# Remotuino-v3.net
KiCad netlist of a schematic drawn in EAGLE
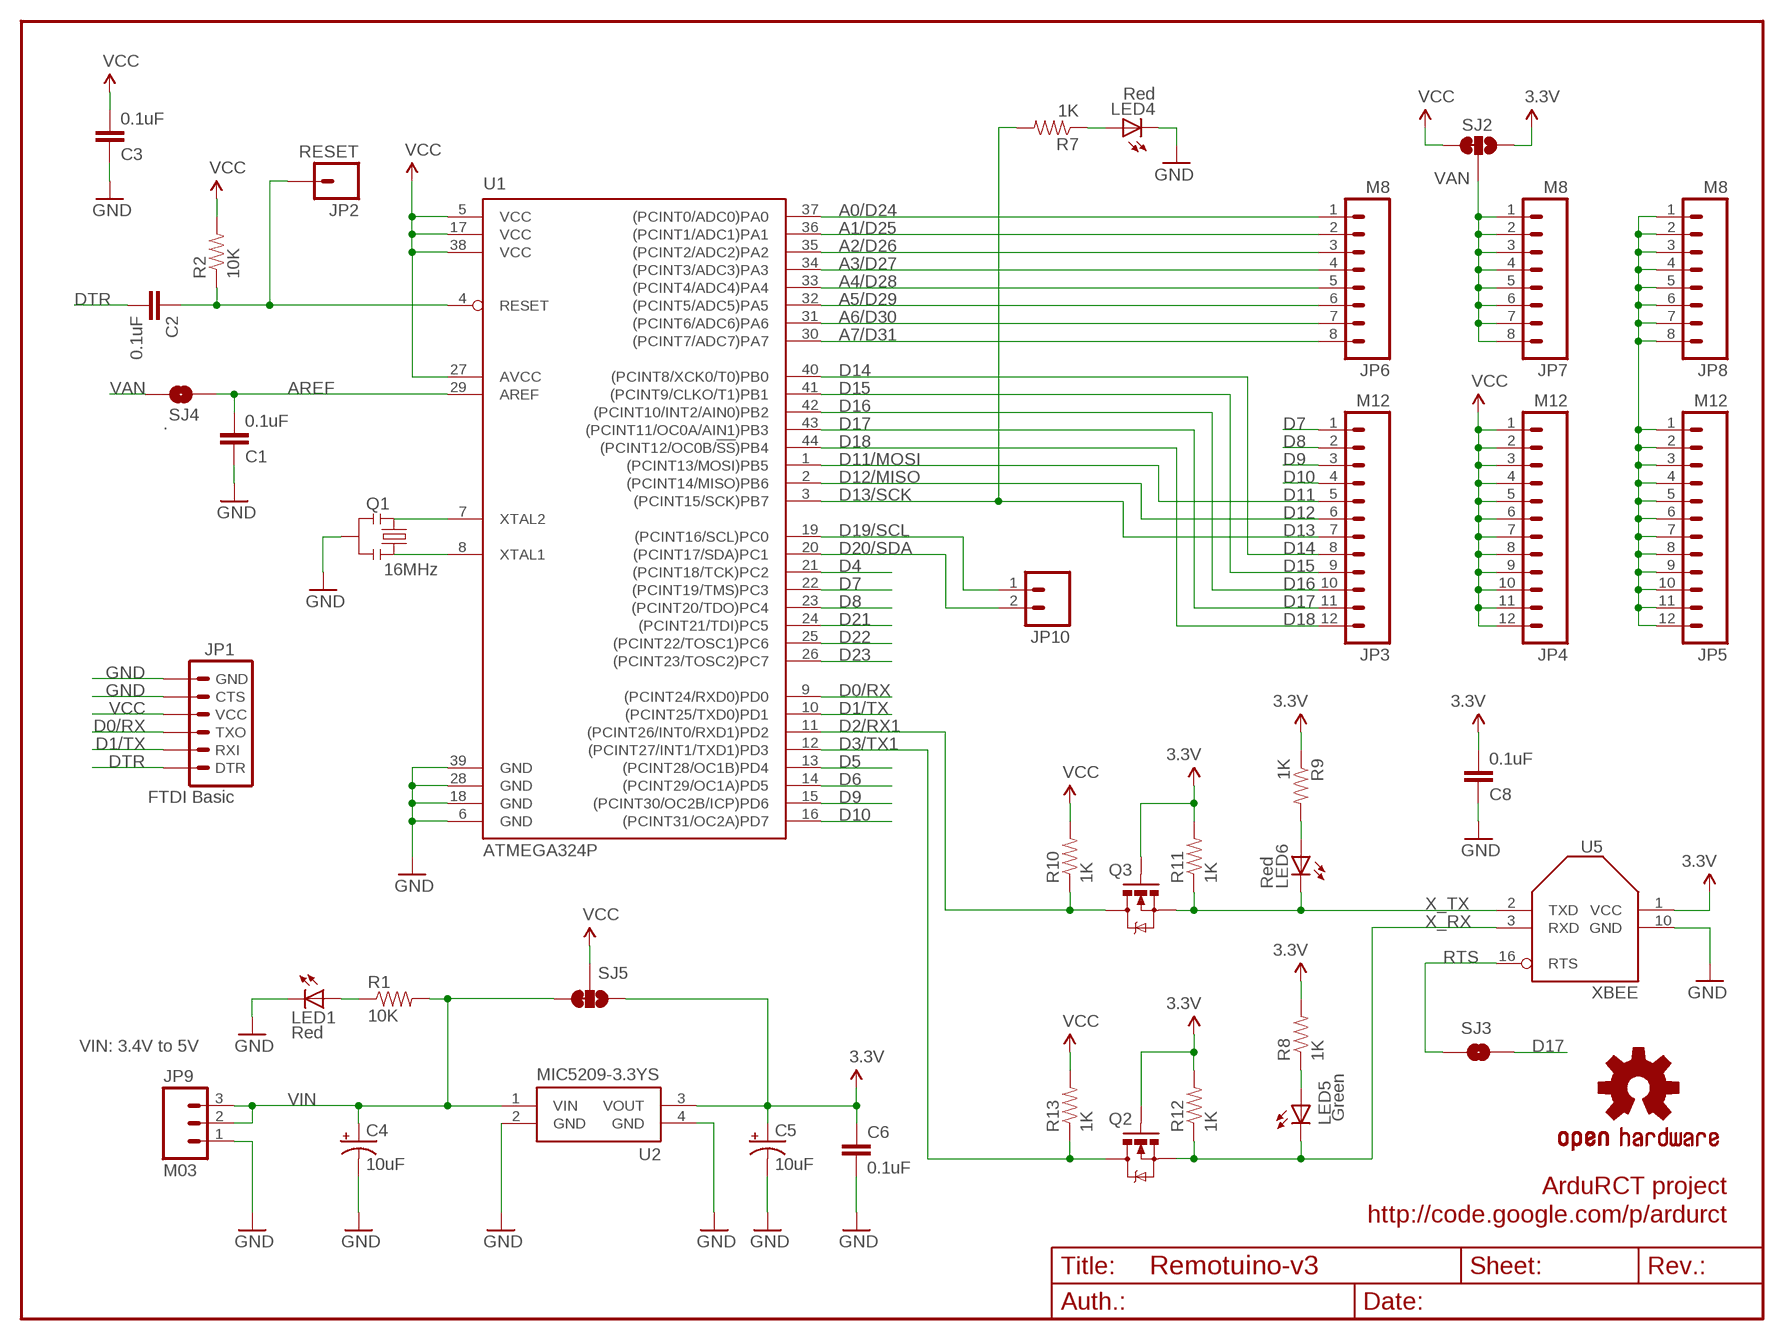
[diagram p0: schematic, sheet 1]

(export (version "E")
  (design (tool "Eeschema 10.0.6"))
  (components
    (comp (ref "C1")
      (value "0.1uF")
      (footprint "eagle-import:0805")
      (libsource (lib "eagle-import") (part "CAP0805"))
    )
    (comp (ref "C2")
      (value "0.1uF")
      (footprint "eagle-import:0805")
      (libsource (lib "eagle-import") (part "CAP0805"))
    )
    (comp (ref "C3")
      (value "0.1uF")
      (footprint "eagle-import:0805")
      (libsource (lib "eagle-import") (part "CAP0805"))
    )
    (comp (ref "C4")
      (value "10uF")
      (footprint "eagle-import:EIA3216")
      (libsource (lib "eagle-import") (part "CAP_POL1206"))
    )
    (comp (ref "C5")
      (value "10uF")
      (footprint "eagle-import:EIA3216")
      (libsource (lib "eagle-import") (part "CAP_POL1206"))
    )
    (comp (ref "C6")
      (value "0.1uF")
      (footprint "eagle-import:0805")
      (libsource (lib "eagle-import") (part "CAP0805"))
    )
    (comp (ref "C8")
      (value "0.1uF")
      (footprint "eagle-import:0805")
      (libsource (lib "eagle-import") (part "CAP0805"))
    )
    (comp (ref "JP1")
      (value "FTDI Basic")
      (footprint "eagle-import:1X06")
      (libsource (lib "eagle-import") (part "ARDUINO_SERIAL_PROGRAMPTH"))
    )
    (comp (ref "JP2")
      (value "RESET")
      (footprint "eagle-import:1X01")
      (libsource (lib "eagle-import") (part "M01PTH"))
    )
    (comp (ref "JP3")
      (value "M12")
      (footprint "eagle-import:1X12")
      (libsource (lib "eagle-import") (part "M12PTH"))
    )
    (comp (ref "JP4")
      (value "M12")
      (footprint "eagle-import:1X12")
      (libsource (lib "eagle-import") (part "M12PTH"))
    )
    (comp (ref "JP5")
      (value "M12")
      (footprint "eagle-import:1X12")
      (libsource (lib "eagle-import") (part "M12PTH"))
    )
    (comp (ref "JP6")
      (value "M8")
      (footprint "eagle-import:1X08")
      (libsource (lib "eagle-import") (part "M08"))
    )
    (comp (ref "JP7")
      (value "M8")
      (footprint "eagle-import:1X08")
      (libsource (lib "eagle-import") (part "M08"))
    )
    (comp (ref "JP8")
      (value "M8")
      (footprint "eagle-import:1X08")
      (libsource (lib "eagle-import") (part "M08"))
    )
    (comp (ref "JP9")
      (value "M03")
      (footprint "eagle-import:1X3_LONGPAD")
      (libsource (lib "eagle-import") (part "M03"))
    )
    (comp (ref "JP10")
      (value "M02")
      (footprint "eagle-import:1X02")
      (libsource (lib "eagle-import") (part "M02"))
    )
    (comp (ref "LED1")
      (value "Red")
      (footprint "eagle-import:LED-0805")
      (libsource (lib "eagle-import") (part "LED805"))
    )
    (comp (ref "LED4")
      (value "Red")
      (footprint "eagle-import:LED-0805")
      (libsource (lib "eagle-import") (part "LED805"))
    )
    (comp (ref "LED5")
      (value "Green")
      (footprint "eagle-import:LED-0805")
      (libsource (lib "eagle-import") (part "LED805"))
    )
    (comp (ref "LED6")
      (value "Red")
      (footprint "eagle-import:LED-0805")
      (libsource (lib "eagle-import") (part "LED805"))
    )
    (comp (ref "Q1")
      (value "16MHz")
      (footprint "eagle-import:RESONATOR-SMD")
      (libsource (lib "eagle-import") (part "RESONATORSMD"))
    )
    (comp (ref "Q2")
      (value "BSS138")
      (footprint "eagle-import:SOT23-3")
      (libsource (lib "eagle-import") (part "MOSFET-NCHANNELSMD"))
    )
    (comp (ref "Q3")
      (value "BSS138")
      (footprint "eagle-import:SOT23-3")
      (libsource (lib "eagle-import") (part "MOSFET-NCHANNELSMD"))
    )
    (comp (ref "R1")
      (value "10K")
      (footprint "eagle-import:0805")
      (libsource (lib "eagle-import") (part "RESISTOR0805-RES"))
    )
    (comp (ref "R2")
      (value "10K")
      (footprint "eagle-import:0805")
      (libsource (lib "eagle-import") (part "RESISTOR0805-RES"))
    )
    (comp (ref "R7")
      (value "1K")
      (footprint "eagle-import:0805")
      (libsource (lib "eagle-import") (part "RESISTOR0805-RES"))
    )
    (comp (ref "R8")
      (value "1K")
      (footprint "eagle-import:0805")
      (libsource (lib "eagle-import") (part "RESISTOR0805-RES"))
    )
    (comp (ref "R9")
      (value "1K")
      (footprint "eagle-import:0805")
      (libsource (lib "eagle-import") (part "RESISTOR0805-RES"))
    )
    (comp (ref "R10")
      (value "1K")
      (footprint "eagle-import:0805")
      (libsource (lib "eagle-import") (part "RESISTOR0805-RES"))
    )
    (comp (ref "R11")
      (value "1K")
      (footprint "eagle-import:0805")
      (libsource (lib "eagle-import") (part "RESISTOR0805-RES"))
    )
    (comp (ref "R12")
      (value "1K")
      (footprint "eagle-import:0805")
      (libsource (lib "eagle-import") (part "RESISTOR0805-RES"))
    )
    (comp (ref "R13")
      (value "1K")
      (footprint "eagle-import:0805")
      (libsource (lib "eagle-import") (part "RESISTOR0805-RES"))
    )
    (comp (ref "SJ2")
      (value "SJ_2WAYS_1-2W")
      (footprint "eagle-import:SJ_2WAYS_1-2")
      (libsource (lib "eagle-import") (part "SJ_2WAYS_1-2W"))
    )
    (comp (ref "SJ3")
      (value "SOLDERJUMPERNO")
      (footprint "eagle-import:SJ_2S-NO")
      (libsource (lib "eagle-import") (part "SOLDERJUMPERNO"))
    )
    (comp (ref "SJ4")
      (value ".")
      (footprint "eagle-import:SJ_2S-TRACE")
      (libsource (lib "eagle-import") (part "SOLDERJUMPERTRACE"))
    )
    (comp (ref "SJ5")
      (value "SJ_2WAYS_1-2W")
      (footprint "eagle-import:SJ_2WAYS_1-2")
      (libsource (lib "eagle-import") (part "SJ_2WAYS_1-2W"))
    )
    (comp (ref "U$3")
      (value "OSHW-LOGOS")
      (footprint "eagle-import:OSHW-LOGO-S")
      (libsource (lib "eagle-import") (part "OSHW-LOGOS"))
    )
    (comp (ref "U1")
      (value "ATMEGA324P")
      (footprint "eagle-import:TQFP44")
      (libsource (lib "eagle-import") (part "ATMEGA324A"))
    )
    (comp (ref "U2")
      (value "MIC5209-3.3YS")
      (footprint "eagle-import:SOT223")
      (libsource (lib "eagle-import") (part "MIC5209"))
    )
    (comp (ref "U5")
      (value "XBEE")
      (footprint "eagle-import:XBEE-SMD")
      (libsource (lib "eagle-import") (part "XBEE-SIMPLESMD"))
    )
  )
  (nets
    (net (code "1") (name "/A0{slash}D24") (class "Default")
      (node (ref "JP6") (pin "1") (pinfunction "1_1") (pintype "passive"))
      (node (ref "U1") (pin "37") (pinfunction "(PCINT0/ADC0)PA0_37") (pintype "bidirectional"))
    )
    (net (code "2") (name "/A1{slash}D25") (class "Default")
      (node (ref "JP6") (pin "2") (pinfunction "2_2") (pintype "passive"))
      (node (ref "U1") (pin "36") (pinfunction "(PCINT1/ADC1)PA1_36") (pintype "bidirectional"))
    )
    (net (code "3") (name "/A2{slash}D26") (class "Default")
      (node (ref "JP6") (pin "3") (pinfunction "3_3") (pintype "passive"))
      (node (ref "U1") (pin "35") (pinfunction "(PCINT2/ADC2)PA2_35") (pintype "bidirectional"))
    )
    (net (code "4") (name "/A3{slash}D27") (class "Default")
      (node (ref "JP6") (pin "4") (pinfunction "4_4") (pintype "passive"))
      (node (ref "U1") (pin "34") (pinfunction "(PCINT3/ADC3)PA3_34") (pintype "bidirectional"))
    )
    (net (code "5") (name "/A4{slash}D28") (class "Default")
      (node (ref "JP6") (pin "5") (pinfunction "5_5") (pintype "passive"))
      (node (ref "U1") (pin "33") (pinfunction "(PCINT4/ADC4)PA4_33") (pintype "bidirectional"))
    )
    (net (code "6") (name "/A5{slash}D29") (class "Default")
      (node (ref "JP6") (pin "6") (pinfunction "6_6") (pintype "passive"))
      (node (ref "U1") (pin "32") (pinfunction "(PCINT5/ADC5)PA5_32") (pintype "bidirectional"))
    )
    (net (code "7") (name "/A6{slash}D30") (class "Default")
      (node (ref "JP6") (pin "7") (pinfunction "7_7") (pintype "passive"))
      (node (ref "U1") (pin "31") (pinfunction "(PCINT6/ADC6)PA6_31") (pintype "bidirectional"))
    )
    (net (code "8") (name "/A7{slash}D31") (class "Default")
      (node (ref "JP6") (pin "8") (pinfunction "8_8") (pintype "passive"))
      (node (ref "U1") (pin "30") (pinfunction "(PCINT7/ADC7)PA7_30") (pintype "bidirectional"))
    )
    (net (code "9") (name "/AREF") (class "Default")
      (node (ref "C1") (pin "2") (pinfunction "2_2") (pintype "passive"))
      (node (ref "SJ4") (pin "2") (pinfunction "2_2") (pintype "passive"))
      (node (ref "U1") (pin "29") (pinfunction "AREF_29") (pintype "passive"))
    )
    (net (code "10") (name "/D0{slash}RX") (class "Default")
      (node (ref "JP1") (pin "3") (pinfunction "TXO_3") (pintype "passive"))
      (node (ref "U1") (pin "9") (pinfunction "(PCINT24/RXD0)PD0_9") (pintype "bidirectional"))
    )
    (net (code "11") (name "/D1{slash}TX") (class "Default")
      (node (ref "JP1") (pin "2") (pinfunction "RXI_2") (pintype "passive"))
      (node (ref "U1") (pin "10") (pinfunction "(PCINT25/TXD0)PD1_10") (pintype "bidirectional"))
    )
    (net (code "12") (name "/D2{slash}RX1") (class "Default")
      (node (ref "Q3") (pin "3") (pinfunction "D_3") (pintype "passive"))
      (node (ref "R10") (pin "1") (pinfunction "1_1") (pintype "passive"))
      (node (ref "U1") (pin "11") (pinfunction "(PCINT26/INT0/RXD1)PD2_11") (pintype "bidirectional"))
    )
    (net (code "13") (name "/D3{slash}TX1") (class "Default")
      (node (ref "Q2") (pin "3") (pinfunction "D_3") (pintype "passive"))
      (node (ref "R13") (pin "1") (pinfunction "1_1") (pintype "passive"))
      (node (ref "U1") (pin "12") (pinfunction "(PCINT27/INT1/TXD1)PD3_12") (pintype "bidirectional"))
    )
    (net (code "14") (name "/D4") (class "Default")
      (node (ref "U1") (pin "21") (pinfunction "(PCINT18/TCK)PC2_21") (pintype "output"))
    )
    (net (code "15") (name "/D5") (class "Default")
      (node (ref "U1") (pin "13") (pinfunction "(PCINT28/OC1B)PD4_13") (pintype "bidirectional"))
    )
    (net (code "16") (name "/D6") (class "Default")
      (node (ref "U1") (pin "14") (pinfunction "(PCINT29/OC1A)PD5_14") (pintype "bidirectional"))
    )
    (net (code "17") (name "/D7") (class "Default")
      (node (ref "JP3") (pin "1") (pinfunction "1_1") (pintype "passive"))
      (node (ref "U1") (pin "22") (pinfunction "(PCINT19/TMS)PC3_22") (pintype "output"))
    )
    (net (code "18") (name "/D8") (class "Default")
      (node (ref "JP3") (pin "2") (pinfunction "2_2") (pintype "passive"))
      (node (ref "U1") (pin "23") (pinfunction "(PCINT20/TDO)PC4_23") (pintype "output"))
    )
    (net (code "19") (name "/D9") (class "Default")
      (node (ref "JP3") (pin "3") (pinfunction "3_3") (pintype "passive"))
      (node (ref "U1") (pin "15") (pinfunction "(PCINT30/OC2B/ICP)PD6_15") (pintype "bidirectional"))
    )
    (net (code "20") (name "/D10") (class "Default")
      (node (ref "JP3") (pin "4") (pinfunction "4_4") (pintype "passive"))
      (node (ref "U1") (pin "16") (pinfunction "(PCINT31/OC2A)PD7_16") (pintype "bidirectional"))
    )
    (net (code "21") (name "/D11{slash}MOSI") (class "Default")
      (node (ref "JP3") (pin "5") (pinfunction "5_5") (pintype "passive"))
      (node (ref "U1") (pin "1") (pinfunction "(PCINT13/MOSI)PB5_1") (pintype "bidirectional"))
    )
    (net (code "22") (name "/D12{slash}MISO") (class "Default")
      (node (ref "JP3") (pin "6") (pinfunction "6_6") (pintype "passive"))
      (node (ref "U1") (pin "2") (pinfunction "(PCINT14/MISO)PB6_2") (pintype "bidirectional"))
    )
    (net (code "23") (name "/D13{slash}SCK") (class "Default")
      (node (ref "JP3") (pin "7") (pinfunction "7_7") (pintype "passive"))
      (node (ref "R7") (pin "2") (pinfunction "2_2") (pintype "passive"))
      (node (ref "U1") (pin "3") (pinfunction "(PCINT15/SCK)PB7_3") (pintype "bidirectional"))
    )
    (net (code "24") (name "/D14") (class "Default")
      (node (ref "JP3") (pin "8") (pinfunction "8_8") (pintype "passive"))
      (node (ref "U1") (pin "40") (pinfunction "(PCINT8/XCK0/T0)PB0_40") (pintype "bidirectional"))
    )
    (net (code "25") (name "/D15") (class "Default")
      (node (ref "JP3") (pin "9") (pinfunction "9_9") (pintype "passive"))
      (node (ref "U1") (pin "41") (pinfunction "(PCINT9/CLKO/T1)PB1_41") (pintype "bidirectional"))
    )
    (net (code "26") (name "/D16") (class "Default")
      (node (ref "JP3") (pin "10") (pinfunction "10_10") (pintype "passive"))
      (node (ref "U1") (pin "42") (pinfunction "(PCINT10/INT2/AIN0)PB2_42") (pintype "bidirectional"))
    )
    (net (code "27") (name "/D17") (class "Default")
      (node (ref "JP3") (pin "11") (pinfunction "11_11") (pintype "passive"))
      (node (ref "SJ3") (pin "2") (pinfunction "2_2") (pintype "passive"))
      (node (ref "U1") (pin "43") (pinfunction "(PCINT11/OC0A/AIN1)PB3_43") (pintype "bidirectional"))
    )
    (net (code "28") (name "/D18") (class "Default")
      (node (ref "JP3") (pin "12") (pinfunction "12_12") (pintype "passive"))
      (node (ref "U1") (pin "44") (pinfunction "(PCINT12/OC0B/~{SS})PB4_44") (pintype "bidirectional"))
    )
    (net (code "29") (name "/D19{slash}SCL") (class "Default")
      (node (ref "JP10") (pin "1") (pinfunction "1_1") (pintype "passive"))
      (node (ref "U1") (pin "19") (pinfunction "(PCINT16/SCL)PC0_19") (pintype "output"))
    )
    (net (code "30") (name "/D20{slash}SDA") (class "Default")
      (node (ref "JP10") (pin "2") (pinfunction "2_2") (pintype "passive"))
      (node (ref "U1") (pin "20") (pinfunction "(PCINT17/SDA)PC1_20") (pintype "output"))
    )
    (net (code "31") (name "/D21") (class "Default")
      (node (ref "U1") (pin "24") (pinfunction "(PCINT21/TDI)PC5_24") (pintype "output"))
    )
    (net (code "32") (name "/D22") (class "Default")
      (node (ref "U1") (pin "25") (pinfunction "(PCINT22/TOSC1)PC6_25") (pintype "output"))
    )
    (net (code "33") (name "/D23") (class "Default")
      (node (ref "U1") (pin "26") (pinfunction "(PCINT23/TOSC2)PC7_26") (pintype "output"))
    )
    (net (code "34") (name "/DTR") (class "Default")
      (node (ref "C2") (pin "2") (pinfunction "2_2") (pintype "passive"))
      (node (ref "JP1") (pin "1") (pinfunction "DTR_1") (pintype "passive"))
    )
    (net (code "35") (name "/RTS") (class "Default")
      (node (ref "SJ3") (pin "1") (pinfunction "1_1") (pintype "passive"))
      (node (ref "U5") (pin "16") (pinfunction "RTS_16") (pintype "bidirectional"))
    )
    (net (code "36") (name "/VAN") (class "Default")
      (node (ref "JP7") (pin "1") (pinfunction "1_1") (pintype "passive"))
      (node (ref "JP7") (pin "2") (pinfunction "2_2") (pintype "passive"))
      (node (ref "JP7") (pin "3") (pinfunction "3_3") (pintype "passive"))
      (node (ref "JP7") (pin "4") (pinfunction "4_4") (pintype "passive"))
      (node (ref "JP7") (pin "5") (pinfunction "5_5") (pintype "passive"))
      (node (ref "JP7") (pin "6") (pinfunction "6_6") (pintype "passive"))
      (node (ref "JP7") (pin "7") (pinfunction "7_7") (pintype "passive"))
      (node (ref "JP7") (pin "8") (pinfunction "8_8") (pintype "passive"))
      (node (ref "SJ2") (pin "2") (pinfunction "2_2") (pintype "passive"))
      (node (ref "SJ4") (pin "1") (pinfunction "1_1") (pintype "passive"))
    )
    (net (code "37") (name "/VIN") (class "Default")
      (node (ref "C4") (pin "A") (pinfunction "+_A") (pintype "passive"))
      (node (ref "JP9") (pin "2") (pinfunction "2_2") (pintype "passive"))
      (node (ref "JP9") (pin "3") (pinfunction "3_3") (pintype "passive"))
      (node (ref "R1") (pin "2") (pinfunction "2_2") (pintype "passive"))
      (node (ref "SJ5") (pin "1") (pinfunction "1_1") (pintype "passive"))
      (node (ref "U2") (pin "1") (pinfunction "VIN_1") (pintype "bidirectional"))
    )
    (net (code "38") (name "/X_RX") (class "Default")
      (node (ref "LED5") (pin "2") (pinfunction "C_2") (pintype "passive"))
      (node (ref "Q2") (pin "2") (pinfunction "S_2") (pintype "passive"))
      (node (ref "R12") (pin "1") (pinfunction "1_1") (pintype "passive"))
      (node (ref "U5") (pin "3") (pinfunction "RXD_3") (pintype "bidirectional"))
    )
    (net (code "39") (name "/X_TX") (class "Default")
      (node (ref "LED6") (pin "2") (pinfunction "C_2") (pintype "passive"))
      (node (ref "Q3") (pin "2") (pinfunction "S_2") (pintype "passive"))
      (node (ref "R11") (pin "1") (pinfunction "1_1") (pintype "passive"))
      (node (ref "U5") (pin "2") (pinfunction "TXD_2") (pintype "bidirectional"))
    )
    (net (code "40") (name "3.3V") (class "Default")
      (node (ref "C5") (pin "A") (pinfunction "+_A") (pintype "passive"))
      (node (ref "C6") (pin "1") (pinfunction "1_1") (pintype "passive"))
      (node (ref "C8") (pin "2") (pinfunction "2_2") (pintype "passive"))
      (node (ref "Q2") (pin "1") (pinfunction "G_1") (pintype "passive"))
      (node (ref "Q3") (pin "1") (pinfunction "G_1") (pintype "passive"))
      (node (ref "R11") (pin "2") (pinfunction "2_2") (pintype "passive"))
      (node (ref "R12") (pin "2") (pinfunction "2_2") (pintype "passive"))
      (node (ref "R8") (pin "2") (pinfunction "2_2") (pintype "passive"))
      (node (ref "R9") (pin "1") (pinfunction "1_1") (pintype "passive"))
      (node (ref "SJ2") (pin "3") (pinfunction "3_3") (pintype "passive"))
      (node (ref "SJ5") (pin "3") (pinfunction "3_3") (pintype "passive"))
      (node (ref "U2") (pin "3") (pinfunction "VOUT_3") (pintype "bidirectional"))
      (node (ref "U5") (pin "1") (pinfunction "VCC_1") (pintype "bidirectional"))
    )
    (net (code "41") (name "GND") (class "Default")
      (node (ref "C1") (pin "1") (pinfunction "1_1") (pintype "passive"))
      (node (ref "C3") (pin "1") (pinfunction "1_1") (pintype "passive"))
      (node (ref "C4") (pin "C") (pinfunction "-_C") (pintype "passive"))
      (node (ref "C5") (pin "C") (pinfunction "-_C") (pintype "passive"))
      (node (ref "C6") (pin "2") (pinfunction "2_2") (pintype "passive"))
      (node (ref "C8") (pin "1") (pinfunction "1_1") (pintype "passive"))
      (node (ref "JP1") (pin "5") (pinfunction "CTS_5") (pintype "passive"))
      (node (ref "JP1") (pin "6") (pinfunction "GND_6") (pintype "passive"))
      (node (ref "JP9") (pin "1") (pinfunction "1_1") (pintype "passive"))
      (node (ref "LED1") (pin "2") (pinfunction "C_2") (pintype "passive"))
      (node (ref "LED4") (pin "2") (pinfunction "C_2") (pintype "passive"))
      (node (ref "Q1") (pin "2") (pinfunction "2_2") (pintype "passive"))
      (node (ref "U1") (pin "18") (pinfunction "GND_18") (pintype "power_in"))
      (node (ref "U1") (pin "28") (pinfunction "GND_28") (pintype "power_in"))
      (node (ref "U1") (pin "39") (pinfunction "GND_39") (pintype "power_in"))
      (node (ref "U1") (pin "6") (pinfunction "GND_6") (pintype "power_in"))
      (node (ref "U2") (pin "2") (pinfunction "GND_2") (pintype "bidirectional"))
      (node (ref "U2") (pin "4") (pinfunction "GND_4") (pintype "bidirectional"))
      (node (ref "U5") (pin "10") (pinfunction "GND_10") (pintype "bidirectional"))
    )
    (net (code "42") (name "Net-(JP5-Pad1)") (class "Default")
      (node (ref "JP5") (pin "1") (pinfunction "1_1") (pintype "passive"))
      (node (ref "JP5") (pin "10") (pinfunction "10_10") (pintype "passive"))
      (node (ref "JP5") (pin "11") (pinfunction "11_11") (pintype "passive"))
      (node (ref "JP5") (pin "12") (pinfunction "12_12") (pintype "passive"))
      (node (ref "JP5") (pin "2") (pinfunction "2_2") (pintype "passive"))
      (node (ref "JP5") (pin "3") (pinfunction "3_3") (pintype "passive"))
      (node (ref "JP5") (pin "4") (pinfunction "4_4") (pintype "passive"))
      (node (ref "JP5") (pin "5") (pinfunction "5_5") (pintype "passive"))
      (node (ref "JP5") (pin "6") (pinfunction "6_6") (pintype "passive"))
      (node (ref "JP5") (pin "7") (pinfunction "7_7") (pintype "passive"))
      (node (ref "JP5") (pin "8") (pinfunction "8_8") (pintype "passive"))
      (node (ref "JP5") (pin "9") (pinfunction "9_9") (pintype "passive"))
      (node (ref "JP8") (pin "1") (pinfunction "1_1") (pintype "passive"))
      (node (ref "JP8") (pin "2") (pinfunction "2_2") (pintype "passive"))
      (node (ref "JP8") (pin "3") (pinfunction "3_3") (pintype "passive"))
      (node (ref "JP8") (pin "4") (pinfunction "4_4") (pintype "passive"))
      (node (ref "JP8") (pin "5") (pinfunction "5_5") (pintype "passive"))
      (node (ref "JP8") (pin "6") (pinfunction "6_6") (pintype "passive"))
      (node (ref "JP8") (pin "7") (pinfunction "7_7") (pintype "passive"))
      (node (ref "JP8") (pin "8") (pinfunction "8_8") (pintype "passive"))
    )
    (net (code "43") (name "Net-(LED1-A)") (class "Default")
      (node (ref "LED1") (pin "1") (pinfunction "A_1") (pintype "passive"))
      (node (ref "R1") (pin "1") (pinfunction "1_1") (pintype "passive"))
    )
    (net (code "44") (name "Net-(LED4-A)") (class "Default")
      (node (ref "LED4") (pin "1") (pinfunction "A_1") (pintype "passive"))
      (node (ref "R7") (pin "1") (pinfunction "1_1") (pintype "passive"))
    )
    (net (code "45") (name "Net-(LED5-A)") (class "Default")
      (node (ref "LED5") (pin "1") (pinfunction "A_1") (pintype "passive"))
      (node (ref "R8") (pin "1") (pinfunction "1_1") (pintype "passive"))
    )
    (net (code "46") (name "Net-(LED6-A)") (class "Default")
      (node (ref "LED6") (pin "1") (pinfunction "A_1") (pintype "passive"))
      (node (ref "R9") (pin "2") (pinfunction "2_2") (pintype "passive"))
    )
    (net (code "47") (name "Net-(U1-RESET)") (class "Default")
      (node (ref "C2") (pin "1") (pinfunction "1_1") (pintype "passive"))
      (node (ref "JP2") (pin "1") (pinfunction "1_1") (pintype "passive"))
      (node (ref "R2") (pin "1") (pinfunction "1_1") (pintype "passive"))
      (node (ref "U1") (pin "4") (pinfunction "RESET_4") (pintype "input"))
    )
    (net (code "48") (name "Net-(U1-XTAL1)") (class "Default")
      (node (ref "Q1") (pin "1") (pinfunction "1_1") (pintype "passive"))
      (node (ref "U1") (pin "8") (pinfunction "XTAL1_8") (pintype "bidirectional"))
    )
    (net (code "49") (name "Net-(U1-XTAL2)") (class "Default")
      (node (ref "Q1") (pin "3") (pinfunction "3_3") (pintype "passive"))
      (node (ref "U1") (pin "7") (pinfunction "XTAL2_7") (pintype "bidirectional"))
    )
    (net (code "50") (name "VCC") (class "Default")
      (node (ref "C3") (pin "2") (pinfunction "2_2") (pintype "passive"))
      (node (ref "JP1") (pin "4") (pinfunction "VCC_4") (pintype "passive"))
      (node (ref "JP4") (pin "1") (pinfunction "1_1") (pintype "passive"))
      (node (ref "JP4") (pin "10") (pinfunction "10_10") (pintype "passive"))
      (node (ref "JP4") (pin "11") (pinfunction "11_11") (pintype "passive"))
      (node (ref "JP4") (pin "12") (pinfunction "12_12") (pintype "passive"))
      (node (ref "JP4") (pin "2") (pinfunction "2_2") (pintype "passive"))
      (node (ref "JP4") (pin "3") (pinfunction "3_3") (pintype "passive"))
      (node (ref "JP4") (pin "4") (pinfunction "4_4") (pintype "passive"))
      (node (ref "JP4") (pin "5") (pinfunction "5_5") (pintype "passive"))
      (node (ref "JP4") (pin "6") (pinfunction "6_6") (pintype "passive"))
      (node (ref "JP4") (pin "7") (pinfunction "7_7") (pintype "passive"))
      (node (ref "JP4") (pin "8") (pinfunction "8_8") (pintype "passive"))
      (node (ref "JP4") (pin "9") (pinfunction "9_9") (pintype "passive"))
      (node (ref "R10") (pin "2") (pinfunction "2_2") (pintype "passive"))
      (node (ref "R13") (pin "2") (pinfunction "2_2") (pintype "passive"))
      (node (ref "R2") (pin "2") (pinfunction "2_2") (pintype "passive"))
      (node (ref "SJ2") (pin "1") (pinfunction "1_1") (pintype "passive"))
      (node (ref "SJ5") (pin "2") (pinfunction "2_2") (pintype "passive"))
      (node (ref "U1") (pin "17") (pinfunction "VCC_17") (pintype "power_in"))
      (node (ref "U1") (pin "27") (pinfunction "AVCC_27") (pintype "power_in"))
      (node (ref "U1") (pin "38") (pinfunction "VCC_38") (pintype "power_in"))
      (node (ref "U1") (pin "5") (pinfunction "VCC_5") (pintype "power_in"))
    )
  )
)
